# Backplane_Compact_R2_1.net
KiCad netlist of a schematic drawn in EAGLE
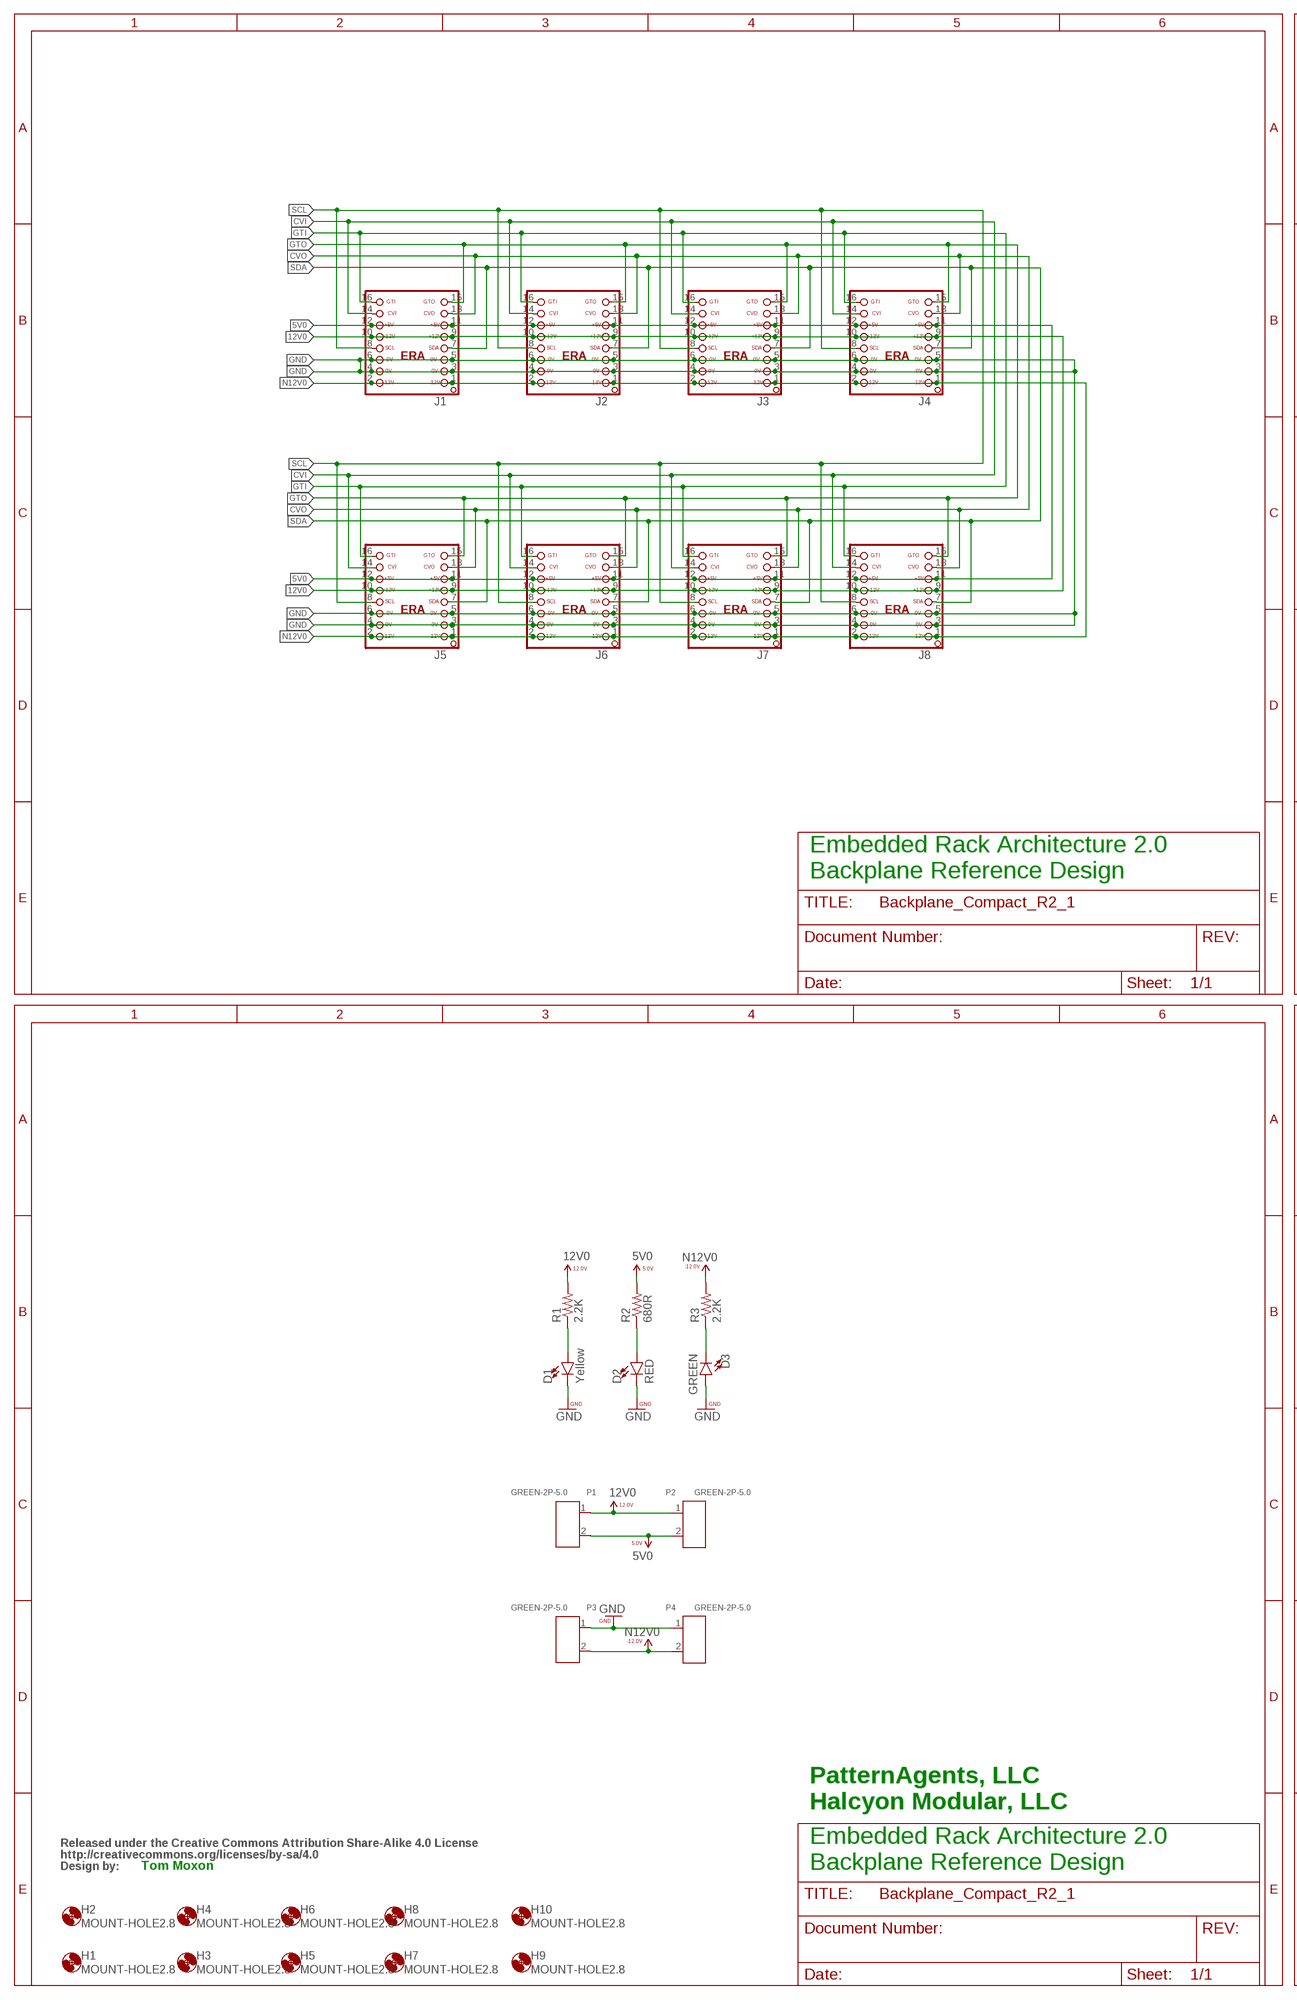
[diagram p0: schematic, sheet 1, part 1 of 2]
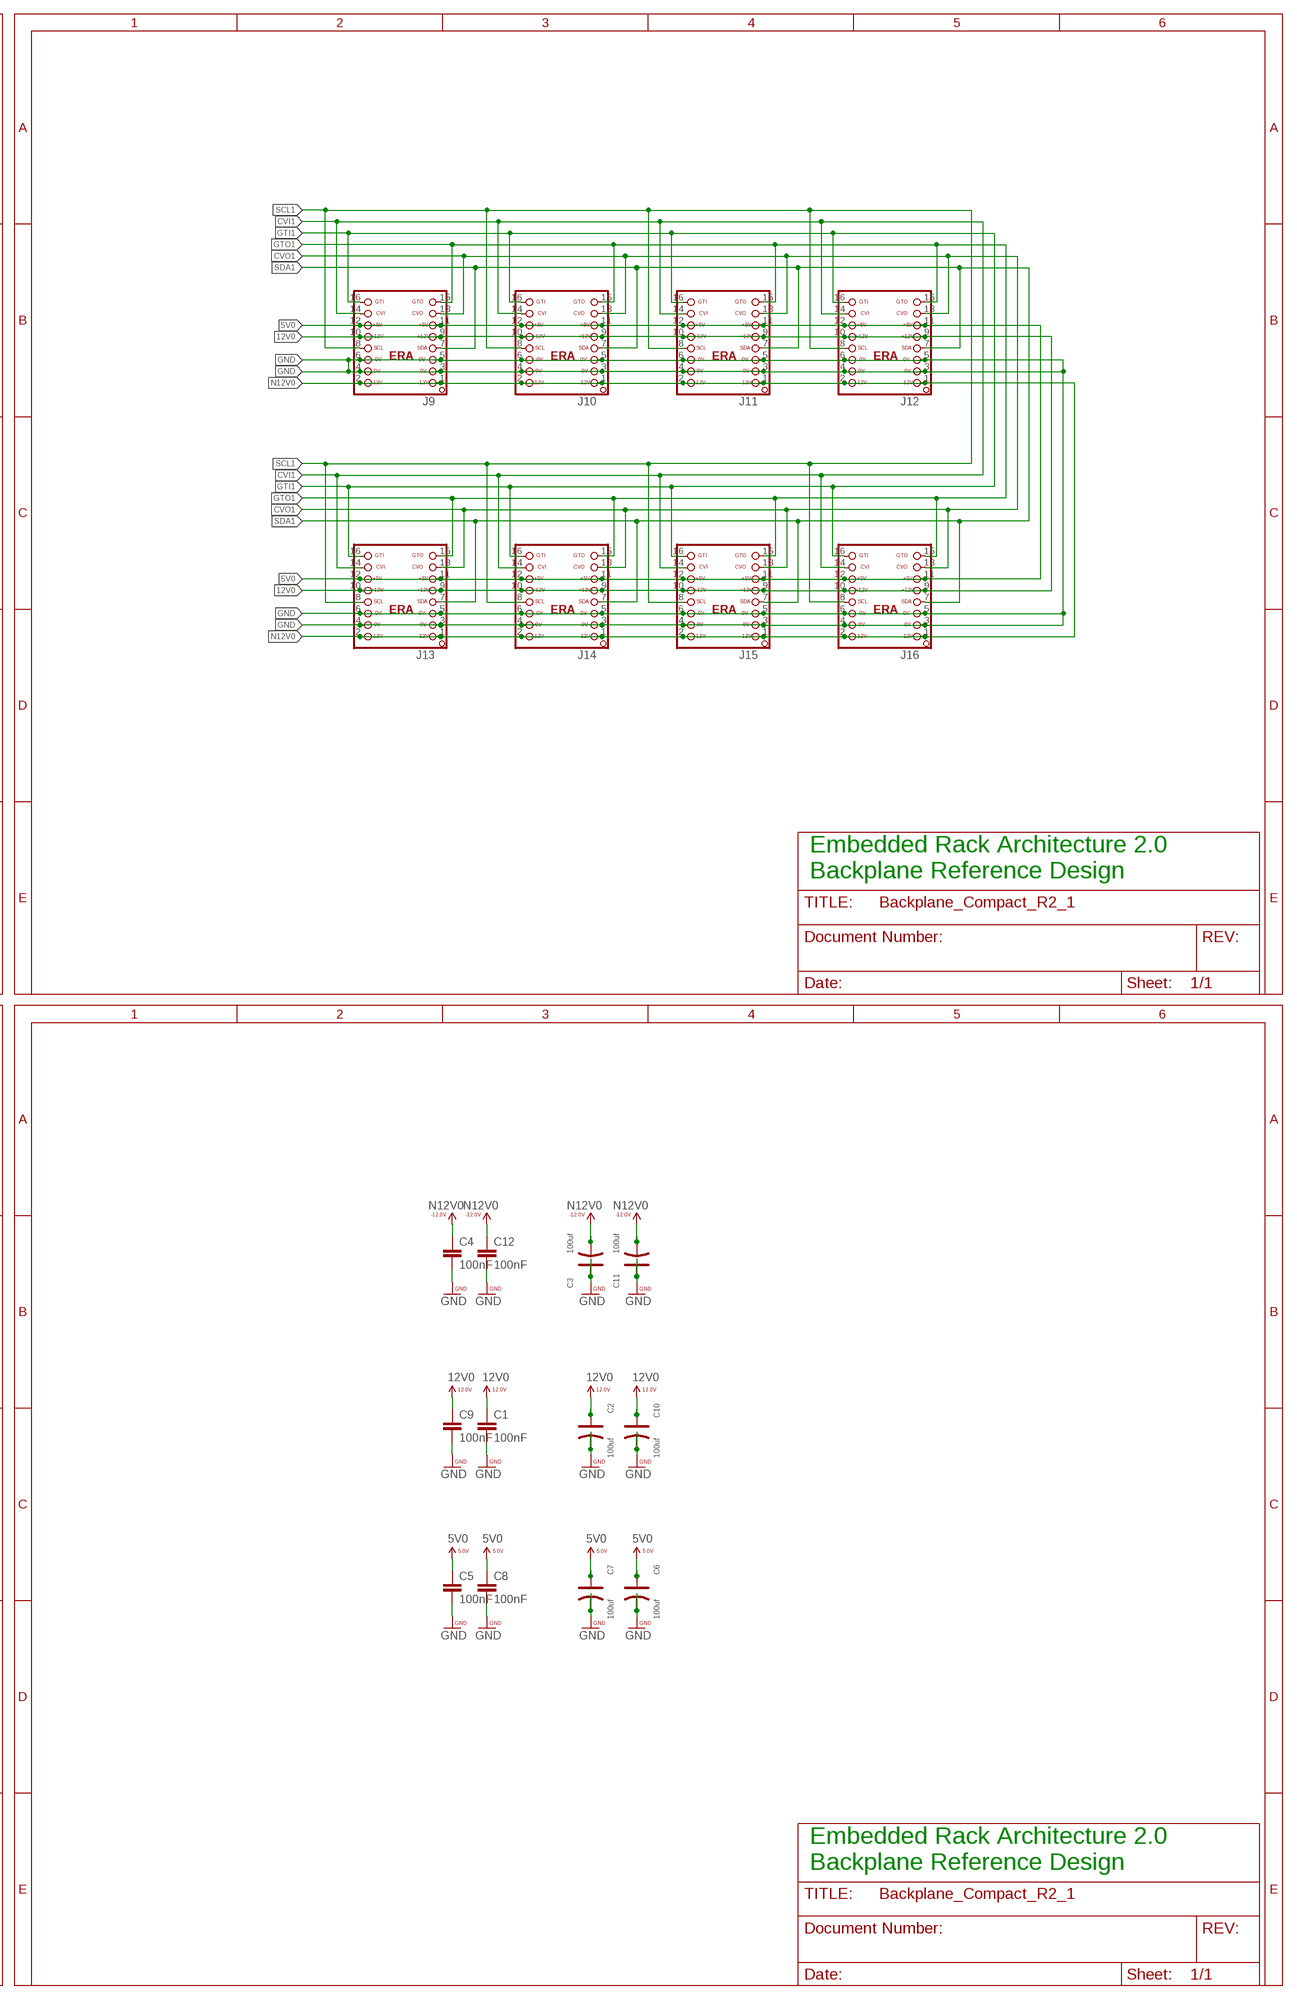
[diagram p1: schematic, sheet 1, part 2 of 2]

(export (version "E")
  (design (tool "Eeschema 10.0.6"))
  (components
    (comp (ref "C1")
      (value "100nF")
      (footprint "eagle-import:0603-CAP")
      (libsource (lib "eagle-import") (part "CAP0603-CAP"))
    )
    (comp (ref "C2")
      (value "100uf")
      (footprint "eagle-import:PC-D5.3MM")
      (fields (field (name "MPN") "KS 100uF/16V"))
      (libsource (lib "eagle-import") (part "DIP-ALUMINUM-100UF-16V(D5-H7MM)"))
    )
    (comp (ref "C3")
      (value "100uf")
      (footprint "eagle-import:PC-D5.3MM")
      (fields (field (name "MPN") "KS 100uF/16V"))
      (libsource (lib "eagle-import") (part "DIP-ALUMINUM-100UF-16V(D5-H7MM)"))
    )
    (comp (ref "C4")
      (value "100nF")
      (footprint "eagle-import:0603-CAP")
      (libsource (lib "eagle-import") (part "CAP0603-CAP"))
    )
    (comp (ref "C5")
      (value "100nF")
      (footprint "eagle-import:0603-CAP")
      (libsource (lib "eagle-import") (part "CAP0603-CAP"))
    )
    (comp (ref "C6")
      (value "100uf")
      (footprint "eagle-import:PC-D5.3MM")
      (fields (field (name "MPN") "KS 100uF/16V"))
      (libsource (lib "eagle-import") (part "DIP-ALUMINUM-100UF-16V(D5-H7MM)"))
    )
    (comp (ref "C7")
      (value "100uf")
      (footprint "eagle-import:PC-D5.3MM")
      (fields (field (name "MPN") "KS 100uF/16V"))
      (libsource (lib "eagle-import") (part "DIP-ALUMINUM-100UF-16V(D5-H7MM)"))
    )
    (comp (ref "C8")
      (value "100nF")
      (footprint "eagle-import:0603-CAP")
      (libsource (lib "eagle-import") (part "CAP0603-CAP"))
    )
    (comp (ref "C9")
      (value "100nF")
      (footprint "eagle-import:0603-CAP")
      (libsource (lib "eagle-import") (part "CAP0603-CAP"))
    )
    (comp (ref "C10")
      (value "100uf")
      (footprint "eagle-import:PC-D5.3MM")
      (fields (field (name "MPN") "KS 100uF/16V"))
      (libsource (lib "eagle-import") (part "DIP-ALUMINUM-100UF-16V(D5-H7MM)"))
    )
    (comp (ref "C11")
      (value "100uf")
      (footprint "eagle-import:PC-D5.3MM")
      (fields (field (name "MPN") "KS 100uF/16V"))
      (libsource (lib "eagle-import") (part "DIP-ALUMINUM-100UF-16V(D5-H7MM)"))
    )
    (comp (ref "C12")
      (value "100nF")
      (footprint "eagle-import:0603-CAP")
      (libsource (lib "eagle-import") (part "CAP0603-CAP"))
    )
    (comp (ref "D1")
      (value "Yellow")
      (footprint "eagle-import:LED-0603")
      (libsource (lib "eagle-import") (part "LED-YELLOW0603"))
    )
    (comp (ref "D2")
      (value "RED")
      (footprint "eagle-import:LED-0603")
      (libsource (lib "eagle-import") (part "LED-RED0603"))
    )
    (comp (ref "D3")
      (value "GREEN")
      (footprint "eagle-import:LED-0603")
      (libsource (lib "eagle-import") (part "LED-GREEN0603"))
    )
    (comp (ref "H1")
      (value "MOUNT-HOLE2.8")
      (footprint "eagle-import:2,8")
      (libsource (lib "eagle-import") (part "MOUNT-HOLE2.8"))
    )
    (comp (ref "H2")
      (value "MOUNT-HOLE2.8")
      (footprint "eagle-import:2,8")
      (libsource (lib "eagle-import") (part "MOUNT-HOLE2.8"))
    )
    (comp (ref "H3")
      (value "MOUNT-HOLE2.8")
      (footprint "eagle-import:2,8")
      (libsource (lib "eagle-import") (part "MOUNT-HOLE2.8"))
    )
    (comp (ref "H4")
      (value "MOUNT-HOLE2.8")
      (footprint "eagle-import:2,8")
      (libsource (lib "eagle-import") (part "MOUNT-HOLE2.8"))
    )
    (comp (ref "H5")
      (value "MOUNT-HOLE2.8")
      (footprint "eagle-import:2,8")
      (libsource (lib "eagle-import") (part "MOUNT-HOLE2.8"))
    )
    (comp (ref "H6")
      (value "MOUNT-HOLE2.8")
      (footprint "eagle-import:2,8")
      (libsource (lib "eagle-import") (part "MOUNT-HOLE2.8"))
    )
    (comp (ref "H7")
      (value "MOUNT-HOLE2.8")
      (footprint "eagle-import:2,8")
      (libsource (lib "eagle-import") (part "MOUNT-HOLE2.8"))
    )
    (comp (ref "H8")
      (value "MOUNT-HOLE2.8")
      (footprint "eagle-import:2,8")
      (libsource (lib "eagle-import") (part "MOUNT-HOLE2.8"))
    )
    (comp (ref "H9")
      (value "MOUNT-HOLE2.8")
      (footprint "eagle-import:2,8")
      (libsource (lib "eagle-import") (part "MOUNT-HOLE2.8"))
    )
    (comp (ref "H10")
      (value "MOUNT-HOLE2.8")
      (footprint "eagle-import:2,8")
      (libsource (lib "eagle-import") (part "MOUNT-HOLE2.8"))
    )
    (comp (ref "J1")
      (value "ERA-SHROUD")
      (footprint "eagle-import:ERA")
      (libsource (lib "eagle-import") (part "ERA-SHROUD"))
    )
    (comp (ref "J2")
      (value "ERA-SHROUD")
      (footprint "eagle-import:ERA")
      (libsource (lib "eagle-import") (part "ERA-SHROUD"))
    )
    (comp (ref "J3")
      (value "ERA-SHROUD")
      (footprint "eagle-import:ERA")
      (libsource (lib "eagle-import") (part "ERA-SHROUD"))
    )
    (comp (ref "J4")
      (value "ERA-SHROUD")
      (footprint "eagle-import:ERA")
      (libsource (lib "eagle-import") (part "ERA-SHROUD"))
    )
    (comp (ref "J5")
      (value "ERA-SHROUD")
      (footprint "eagle-import:ERA")
      (libsource (lib "eagle-import") (part "ERA-SHROUD"))
    )
    (comp (ref "J6")
      (value "ERA-SHROUD")
      (footprint "eagle-import:ERA")
      (libsource (lib "eagle-import") (part "ERA-SHROUD"))
    )
    (comp (ref "J7")
      (value "ERA-SHROUD")
      (footprint "eagle-import:ERA")
      (libsource (lib "eagle-import") (part "ERA-SHROUD"))
    )
    (comp (ref "J8")
      (value "ERA-SHROUD")
      (footprint "eagle-import:ERA")
      (libsource (lib "eagle-import") (part "ERA-SHROUD"))
    )
    (comp (ref "J9")
      (value "ERA-SHROUD")
      (footprint "eagle-import:ERA")
      (libsource (lib "eagle-import") (part "ERA-SHROUD"))
    )
    (comp (ref "J10")
      (value "ERA-SHROUD")
      (footprint "eagle-import:ERA")
      (libsource (lib "eagle-import") (part "ERA-SHROUD"))
    )
    (comp (ref "J11")
      (value "ERA-SHROUD")
      (footprint "eagle-import:ERA")
      (libsource (lib "eagle-import") (part "ERA-SHROUD"))
    )
    (comp (ref "J12")
      (value "ERA-SHROUD")
      (footprint "eagle-import:ERA")
      (libsource (lib "eagle-import") (part "ERA-SHROUD"))
    )
    (comp (ref "J13")
      (value "ERA-SHROUD")
      (footprint "eagle-import:ERA")
      (libsource (lib "eagle-import") (part "ERA-SHROUD"))
    )
    (comp (ref "J14")
      (value "ERA-SHROUD")
      (footprint "eagle-import:ERA")
      (libsource (lib "eagle-import") (part "ERA-SHROUD"))
    )
    (comp (ref "J15")
      (value "ERA-SHROUD")
      (footprint "eagle-import:ERA")
      (libsource (lib "eagle-import") (part "ERA-SHROUD"))
    )
    (comp (ref "J16")
      (value "ERA-SHROUD")
      (footprint "eagle-import:ERA")
      (libsource (lib "eagle-import") (part "ERA-SHROUD"))
    )
    (comp (ref "P1")
      (value "GREEN-2P-5.0")
      (footprint "eagle-import:H2-5.0-10.5X8.0MM")
      (libsource (lib "eagle-import") (part "SCREW-TERMINAL-GREEN(2P-5.0)"))
    )
    (comp (ref "P2")
      (value "GREEN-2P-5.0")
      (footprint "eagle-import:H2-5.0-10.5X8.0MM")
      (libsource (lib "eagle-import") (part "SCREW-TERMINAL-GREEN(2P-5.0)"))
    )
    (comp (ref "P3")
      (value "GREEN-2P-5.0")
      (footprint "eagle-import:H2-5.0-10.5X8.0MM")
      (libsource (lib "eagle-import") (part "SCREW-TERMINAL-GREEN(2P-5.0)"))
    )
    (comp (ref "P4")
      (value "GREEN-2P-5.0")
      (footprint "eagle-import:H2-5.0-10.5X8.0MM")
      (libsource (lib "eagle-import") (part "SCREW-TERMINAL-GREEN(2P-5.0)"))
    )
    (comp (ref "R1")
      (value "2.2K")
      (footprint "eagle-import:0603-RES")
      (libsource (lib "eagle-import") (part "RESISTOR0603"))
    )
    (comp (ref "R2")
      (value "680R")
      (footprint "eagle-import:0603-RES")
      (libsource (lib "eagle-import") (part "RESISTOR0603"))
    )
    (comp (ref "R3")
      (value "2.2K")
      (footprint "eagle-import:0603-RES")
      (libsource (lib "eagle-import") (part "RESISTOR0603"))
    )
    (comp (ref "U$48")
      (value "BY_CC_SA_TEXTTEXT")
      (footprint "eagle-import:BY_CC_SA_TEXT")
      (libsource (lib "eagle-import") (part "BY_CC_SA_TEXTTEXT"))
    )
  )
  (nets
    (net (code "1") (name "5V0") (class "Default")
      (node (ref "C5") (pin "1") (pinfunction "1_1") (pintype "passive"))
      (node (ref "C6") (pin "+") (pinfunction "+_+") (pintype "passive"))
      (node (ref "C7") (pin "+") (pinfunction "+_+") (pintype "passive"))
      (node (ref "C8") (pin "1") (pinfunction "1_1") (pintype "passive"))
      (node (ref "J1") (pin "11") (pinfunction "11_11") (pintype "passive"))
      (node (ref "J1") (pin "12") (pinfunction "12_12") (pintype "passive"))
      (node (ref "J10") (pin "11") (pinfunction "11_11") (pintype "passive"))
      (node (ref "J10") (pin "12") (pinfunction "12_12") (pintype "passive"))
      (node (ref "J11") (pin "11") (pinfunction "11_11") (pintype "passive"))
      (node (ref "J11") (pin "12") (pinfunction "12_12") (pintype "passive"))
      (node (ref "J12") (pin "11") (pinfunction "11_11") (pintype "passive"))
      (node (ref "J12") (pin "12") (pinfunction "12_12") (pintype "passive"))
      (node (ref "J13") (pin "11") (pinfunction "11_11") (pintype "passive"))
      (node (ref "J13") (pin "12") (pinfunction "12_12") (pintype "passive"))
      (node (ref "J14") (pin "11") (pinfunction "11_11") (pintype "passive"))
      (node (ref "J14") (pin "12") (pinfunction "12_12") (pintype "passive"))
      (node (ref "J15") (pin "11") (pinfunction "11_11") (pintype "passive"))
      (node (ref "J15") (pin "12") (pinfunction "12_12") (pintype "passive"))
      (node (ref "J16") (pin "11") (pinfunction "11_11") (pintype "passive"))
      (node (ref "J16") (pin "12") (pinfunction "12_12") (pintype "passive"))
      (node (ref "J2") (pin "11") (pinfunction "11_11") (pintype "passive"))
      (node (ref "J2") (pin "12") (pinfunction "12_12") (pintype "passive"))
      (node (ref "J3") (pin "11") (pinfunction "11_11") (pintype "passive"))
      (node (ref "J3") (pin "12") (pinfunction "12_12") (pintype "passive"))
      (node (ref "J4") (pin "11") (pinfunction "11_11") (pintype "passive"))
      (node (ref "J4") (pin "12") (pinfunction "12_12") (pintype "passive"))
      (node (ref "J5") (pin "11") (pinfunction "11_11") (pintype "passive"))
      (node (ref "J5") (pin "12") (pinfunction "12_12") (pintype "passive"))
      (node (ref "J6") (pin "11") (pinfunction "11_11") (pintype "passive"))
      (node (ref "J6") (pin "12") (pinfunction "12_12") (pintype "passive"))
      (node (ref "J7") (pin "11") (pinfunction "11_11") (pintype "passive"))
      (node (ref "J7") (pin "12") (pinfunction "12_12") (pintype "passive"))
      (node (ref "J8") (pin "11") (pinfunction "11_11") (pintype "passive"))
      (node (ref "J8") (pin "12") (pinfunction "12_12") (pintype "passive"))
      (node (ref "J9") (pin "11") (pinfunction "11_11") (pintype "passive"))
      (node (ref "J9") (pin "12") (pinfunction "12_12") (pintype "passive"))
      (node (ref "P1") (pin "2") (pinfunction "2_2") (pintype "bidirectional"))
      (node (ref "P2") (pin "2") (pinfunction "2_2") (pintype "bidirectional"))
      (node (ref "R2") (pin "2") (pinfunction "2_2") (pintype "passive"))
    )
    (net (code "2") (name "12V0") (class "Default")
      (node (ref "C1") (pin "1") (pinfunction "1_1") (pintype "passive"))
      (node (ref "C10") (pin "+") (pinfunction "+_+") (pintype "passive"))
      (node (ref "C2") (pin "+") (pinfunction "+_+") (pintype "passive"))
      (node (ref "C9") (pin "1") (pinfunction "1_1") (pintype "passive"))
      (node (ref "J1") (pin "10") (pinfunction "10_10") (pintype "passive"))
      (node (ref "J1") (pin "9") (pinfunction "9_9") (pintype "passive"))
      (node (ref "J10") (pin "10") (pinfunction "10_10") (pintype "passive"))
      (node (ref "J10") (pin "9") (pinfunction "9_9") (pintype "passive"))
      (node (ref "J11") (pin "10") (pinfunction "10_10") (pintype "passive"))
      (node (ref "J11") (pin "9") (pinfunction "9_9") (pintype "passive"))
      (node (ref "J12") (pin "10") (pinfunction "10_10") (pintype "passive"))
      (node (ref "J12") (pin "9") (pinfunction "9_9") (pintype "passive"))
      (node (ref "J13") (pin "10") (pinfunction "10_10") (pintype "passive"))
      (node (ref "J13") (pin "9") (pinfunction "9_9") (pintype "passive"))
      (node (ref "J14") (pin "10") (pinfunction "10_10") (pintype "passive"))
      (node (ref "J14") (pin "9") (pinfunction "9_9") (pintype "passive"))
      (node (ref "J15") (pin "10") (pinfunction "10_10") (pintype "passive"))
      (node (ref "J15") (pin "9") (pinfunction "9_9") (pintype "passive"))
      (node (ref "J16") (pin "10") (pinfunction "10_10") (pintype "passive"))
      (node (ref "J16") (pin "9") (pinfunction "9_9") (pintype "passive"))
      (node (ref "J2") (pin "10") (pinfunction "10_10") (pintype "passive"))
      (node (ref "J2") (pin "9") (pinfunction "9_9") (pintype "passive"))
      (node (ref "J3") (pin "10") (pinfunction "10_10") (pintype "passive"))
      (node (ref "J3") (pin "9") (pinfunction "9_9") (pintype "passive"))
      (node (ref "J4") (pin "10") (pinfunction "10_10") (pintype "passive"))
      (node (ref "J4") (pin "9") (pinfunction "9_9") (pintype "passive"))
      (node (ref "J5") (pin "10") (pinfunction "10_10") (pintype "passive"))
      (node (ref "J5") (pin "9") (pinfunction "9_9") (pintype "passive"))
      (node (ref "J6") (pin "10") (pinfunction "10_10") (pintype "passive"))
      (node (ref "J6") (pin "9") (pinfunction "9_9") (pintype "passive"))
      (node (ref "J7") (pin "10") (pinfunction "10_10") (pintype "passive"))
      (node (ref "J7") (pin "9") (pinfunction "9_9") (pintype "passive"))
      (node (ref "J8") (pin "10") (pinfunction "10_10") (pintype "passive"))
      (node (ref "J8") (pin "9") (pinfunction "9_9") (pintype "passive"))
      (node (ref "J9") (pin "10") (pinfunction "10_10") (pintype "passive"))
      (node (ref "J9") (pin "9") (pinfunction "9_9") (pintype "passive"))
      (node (ref "P1") (pin "1") (pinfunction "1_1") (pintype "bidirectional"))
      (node (ref "P2") (pin "1") (pinfunction "1_1") (pintype "bidirectional"))
      (node (ref "R1") (pin "2") (pinfunction "2_2") (pintype "passive"))
    )
    (net (code "3") (name "CVI") (class "Default")
      (node (ref "J1") (pin "14") (pinfunction "14_14") (pintype "passive"))
      (node (ref "J2") (pin "14") (pinfunction "14_14") (pintype "passive"))
      (node (ref "J3") (pin "14") (pinfunction "14_14") (pintype "passive"))
      (node (ref "J4") (pin "14") (pinfunction "14_14") (pintype "passive"))
      (node (ref "J5") (pin "14") (pinfunction "14_14") (pintype "passive"))
      (node (ref "J6") (pin "14") (pinfunction "14_14") (pintype "passive"))
      (node (ref "J7") (pin "14") (pinfunction "14_14") (pintype "passive"))
      (node (ref "J8") (pin "14") (pinfunction "14_14") (pintype "passive"))
    )
    (net (code "4") (name "CVI1") (class "Default")
      (node (ref "J10") (pin "14") (pinfunction "14_14") (pintype "passive"))
      (node (ref "J11") (pin "14") (pinfunction "14_14") (pintype "passive"))
      (node (ref "J12") (pin "14") (pinfunction "14_14") (pintype "passive"))
      (node (ref "J13") (pin "14") (pinfunction "14_14") (pintype "passive"))
      (node (ref "J14") (pin "14") (pinfunction "14_14") (pintype "passive"))
      (node (ref "J15") (pin "14") (pinfunction "14_14") (pintype "passive"))
      (node (ref "J16") (pin "14") (pinfunction "14_14") (pintype "passive"))
      (node (ref "J9") (pin "14") (pinfunction "14_14") (pintype "passive"))
    )
    (net (code "5") (name "CVO") (class "Default")
      (node (ref "J1") (pin "13") (pinfunction "13_13") (pintype "passive"))
      (node (ref "J2") (pin "13") (pinfunction "13_13") (pintype "passive"))
      (node (ref "J3") (pin "13") (pinfunction "13_13") (pintype "passive"))
      (node (ref "J4") (pin "13") (pinfunction "13_13") (pintype "passive"))
      (node (ref "J5") (pin "13") (pinfunction "13_13") (pintype "passive"))
      (node (ref "J6") (pin "13") (pinfunction "13_13") (pintype "passive"))
      (node (ref "J7") (pin "13") (pinfunction "13_13") (pintype "passive"))
      (node (ref "J8") (pin "13") (pinfunction "13_13") (pintype "passive"))
    )
    (net (code "6") (name "CVO1") (class "Default")
      (node (ref "J10") (pin "13") (pinfunction "13_13") (pintype "passive"))
      (node (ref "J11") (pin "13") (pinfunction "13_13") (pintype "passive"))
      (node (ref "J12") (pin "13") (pinfunction "13_13") (pintype "passive"))
      (node (ref "J13") (pin "13") (pinfunction "13_13") (pintype "passive"))
      (node (ref "J14") (pin "13") (pinfunction "13_13") (pintype "passive"))
      (node (ref "J15") (pin "13") (pinfunction "13_13") (pintype "passive"))
      (node (ref "J16") (pin "13") (pinfunction "13_13") (pintype "passive"))
      (node (ref "J9") (pin "13") (pinfunction "13_13") (pintype "passive"))
    )
    (net (code "7") (name "GND") (class "Default")
      (node (ref "C1") (pin "2") (pinfunction "2_2") (pintype "passive"))
      (node (ref "C10") (pin "-") (pinfunction "-_-") (pintype "passive"))
      (node (ref "C11") (pin "+") (pinfunction "+_+") (pintype "passive"))
      (node (ref "C12") (pin "2") (pinfunction "2_2") (pintype "passive"))
      (node (ref "C2") (pin "-") (pinfunction "-_-") (pintype "passive"))
      (node (ref "C3") (pin "+") (pinfunction "+_+") (pintype "passive"))
      (node (ref "C4") (pin "2") (pinfunction "2_2") (pintype "passive"))
      (node (ref "C5") (pin "2") (pinfunction "2_2") (pintype "passive"))
      (node (ref "C6") (pin "-") (pinfunction "-_-") (pintype "passive"))
      (node (ref "C7") (pin "-") (pinfunction "-_-") (pintype "passive"))
      (node (ref "C8") (pin "2") (pinfunction "2_2") (pintype "passive"))
      (node (ref "C9") (pin "2") (pinfunction "2_2") (pintype "passive"))
      (node (ref "D1") (pin "C") (pinfunction "C_C") (pintype "passive"))
      (node (ref "D2") (pin "C") (pinfunction "C_C") (pintype "passive"))
      (node (ref "D3") (pin "A") (pinfunction "A_A") (pintype "passive"))
      (node (ref "J1") (pin "3") (pinfunction "3_3") (pintype "passive"))
      (node (ref "J1") (pin "4") (pinfunction "4_4") (pintype "passive"))
      (node (ref "J1") (pin "5") (pinfunction "5_5") (pintype "passive"))
      (node (ref "J1") (pin "6") (pinfunction "6_6") (pintype "passive"))
      (node (ref "J10") (pin "3") (pinfunction "3_3") (pintype "passive"))
      (node (ref "J10") (pin "4") (pinfunction "4_4") (pintype "passive"))
      (node (ref "J10") (pin "5") (pinfunction "5_5") (pintype "passive"))
      (node (ref "J10") (pin "6") (pinfunction "6_6") (pintype "passive"))
      (node (ref "J11") (pin "3") (pinfunction "3_3") (pintype "passive"))
      (node (ref "J11") (pin "4") (pinfunction "4_4") (pintype "passive"))
      (node (ref "J11") (pin "5") (pinfunction "5_5") (pintype "passive"))
      (node (ref "J11") (pin "6") (pinfunction "6_6") (pintype "passive"))
      (node (ref "J12") (pin "3") (pinfunction "3_3") (pintype "passive"))
      (node (ref "J12") (pin "4") (pinfunction "4_4") (pintype "passive"))
      (node (ref "J12") (pin "5") (pinfunction "5_5") (pintype "passive"))
      (node (ref "J12") (pin "6") (pinfunction "6_6") (pintype "passive"))
      (node (ref "J13") (pin "3") (pinfunction "3_3") (pintype "passive"))
      (node (ref "J13") (pin "4") (pinfunction "4_4") (pintype "passive"))
      (node (ref "J13") (pin "5") (pinfunction "5_5") (pintype "passive"))
      (node (ref "J13") (pin "6") (pinfunction "6_6") (pintype "passive"))
      (node (ref "J14") (pin "3") (pinfunction "3_3") (pintype "passive"))
      (node (ref "J14") (pin "4") (pinfunction "4_4") (pintype "passive"))
      (node (ref "J14") (pin "5") (pinfunction "5_5") (pintype "passive"))
      (node (ref "J14") (pin "6") (pinfunction "6_6") (pintype "passive"))
      (node (ref "J15") (pin "3") (pinfunction "3_3") (pintype "passive"))
      (node (ref "J15") (pin "4") (pinfunction "4_4") (pintype "passive"))
      (node (ref "J15") (pin "5") (pinfunction "5_5") (pintype "passive"))
      (node (ref "J15") (pin "6") (pinfunction "6_6") (pintype "passive"))
      (node (ref "J16") (pin "3") (pinfunction "3_3") (pintype "passive"))
      (node (ref "J16") (pin "4") (pinfunction "4_4") (pintype "passive"))
      (node (ref "J16") (pin "5") (pinfunction "5_5") (pintype "passive"))
      (node (ref "J16") (pin "6") (pinfunction "6_6") (pintype "passive"))
      (node (ref "J2") (pin "3") (pinfunction "3_3") (pintype "passive"))
      (node (ref "J2") (pin "4") (pinfunction "4_4") (pintype "passive"))
      (node (ref "J2") (pin "5") (pinfunction "5_5") (pintype "passive"))
      (node (ref "J2") (pin "6") (pinfunction "6_6") (pintype "passive"))
      (node (ref "J3") (pin "3") (pinfunction "3_3") (pintype "passive"))
      (node (ref "J3") (pin "4") (pinfunction "4_4") (pintype "passive"))
      (node (ref "J3") (pin "5") (pinfunction "5_5") (pintype "passive"))
      (node (ref "J3") (pin "6") (pinfunction "6_6") (pintype "passive"))
      (node (ref "J4") (pin "3") (pinfunction "3_3") (pintype "passive"))
      (node (ref "J4") (pin "4") (pinfunction "4_4") (pintype "passive"))
      (node (ref "J4") (pin "5") (pinfunction "5_5") (pintype "passive"))
      (node (ref "J4") (pin "6") (pinfunction "6_6") (pintype "passive"))
      (node (ref "J5") (pin "3") (pinfunction "3_3") (pintype "passive"))
      (node (ref "J5") (pin "4") (pinfunction "4_4") (pintype "passive"))
      (node (ref "J5") (pin "5") (pinfunction "5_5") (pintype "passive"))
      (node (ref "J5") (pin "6") (pinfunction "6_6") (pintype "passive"))
      (node (ref "J6") (pin "3") (pinfunction "3_3") (pintype "passive"))
      (node (ref "J6") (pin "4") (pinfunction "4_4") (pintype "passive"))
      (node (ref "J6") (pin "5") (pinfunction "5_5") (pintype "passive"))
      (node (ref "J6") (pin "6") (pinfunction "6_6") (pintype "passive"))
      (node (ref "J7") (pin "3") (pinfunction "3_3") (pintype "passive"))
      (node (ref "J7") (pin "4") (pinfunction "4_4") (pintype "passive"))
      (node (ref "J7") (pin "5") (pinfunction "5_5") (pintype "passive"))
      (node (ref "J7") (pin "6") (pinfunction "6_6") (pintype "passive"))
      (node (ref "J8") (pin "3") (pinfunction "3_3") (pintype "passive"))
      (node (ref "J8") (pin "4") (pinfunction "4_4") (pintype "passive"))
      (node (ref "J8") (pin "5") (pinfunction "5_5") (pintype "passive"))
      (node (ref "J8") (pin "6") (pinfunction "6_6") (pintype "passive"))
      (node (ref "J9") (pin "3") (pinfunction "3_3") (pintype "passive"))
      (node (ref "J9") (pin "4") (pinfunction "4_4") (pintype "passive"))
      (node (ref "J9") (pin "5") (pinfunction "5_5") (pintype "passive"))
      (node (ref "J9") (pin "6") (pinfunction "6_6") (pintype "passive"))
      (node (ref "P3") (pin "1") (pinfunction "1_1") (pintype "bidirectional"))
      (node (ref "P4") (pin "1") (pinfunction "1_1") (pintype "bidirectional"))
    )
    (net (code "8") (name "GTI") (class "Default")
      (node (ref "J1") (pin "16") (pinfunction "16_16") (pintype "passive"))
      (node (ref "J2") (pin "16") (pinfunction "16_16") (pintype "passive"))
      (node (ref "J3") (pin "16") (pinfunction "16_16") (pintype "passive"))
      (node (ref "J4") (pin "16") (pinfunction "16_16") (pintype "passive"))
      (node (ref "J5") (pin "16") (pinfunction "16_16") (pintype "passive"))
      (node (ref "J6") (pin "16") (pinfunction "16_16") (pintype "passive"))
      (node (ref "J7") (pin "16") (pinfunction "16_16") (pintype "passive"))
      (node (ref "J8") (pin "16") (pinfunction "16_16") (pintype "passive"))
    )
    (net (code "9") (name "GTI1") (class "Default")
      (node (ref "J10") (pin "16") (pinfunction "16_16") (pintype "passive"))
      (node (ref "J11") (pin "16") (pinfunction "16_16") (pintype "passive"))
      (node (ref "J12") (pin "16") (pinfunction "16_16") (pintype "passive"))
      (node (ref "J13") (pin "16") (pinfunction "16_16") (pintype "passive"))
      (node (ref "J14") (pin "16") (pinfunction "16_16") (pintype "passive"))
      (node (ref "J15") (pin "16") (pinfunction "16_16") (pintype "passive"))
      (node (ref "J16") (pin "16") (pinfunction "16_16") (pintype "passive"))
      (node (ref "J9") (pin "16") (pinfunction "16_16") (pintype "passive"))
    )
    (net (code "10") (name "GTO") (class "Default")
      (node (ref "J1") (pin "15") (pinfunction "15_15") (pintype "passive"))
      (node (ref "J2") (pin "15") (pinfunction "15_15") (pintype "passive"))
      (node (ref "J3") (pin "15") (pinfunction "15_15") (pintype "passive"))
      (node (ref "J4") (pin "15") (pinfunction "15_15") (pintype "passive"))
      (node (ref "J5") (pin "15") (pinfunction "15_15") (pintype "passive"))
      (node (ref "J6") (pin "15") (pinfunction "15_15") (pintype "passive"))
      (node (ref "J7") (pin "15") (pinfunction "15_15") (pintype "passive"))
      (node (ref "J8") (pin "15") (pinfunction "15_15") (pintype "passive"))
    )
    (net (code "11") (name "GTO1") (class "Default")
      (node (ref "J10") (pin "15") (pinfunction "15_15") (pintype "passive"))
      (node (ref "J11") (pin "15") (pinfunction "15_15") (pintype "passive"))
      (node (ref "J12") (pin "15") (pinfunction "15_15") (pintype "passive"))
      (node (ref "J13") (pin "15") (pinfunction "15_15") (pintype "passive"))
      (node (ref "J14") (pin "15") (pinfunction "15_15") (pintype "passive"))
      (node (ref "J15") (pin "15") (pinfunction "15_15") (pintype "passive"))
      (node (ref "J16") (pin "15") (pinfunction "15_15") (pintype "passive"))
      (node (ref "J9") (pin "15") (pinfunction "15_15") (pintype "passive"))
    )
    (net (code "12") (name "N12V0") (class "Default")
      (node (ref "C11") (pin "-") (pinfunction "-_-") (pintype "passive"))
      (node (ref "C12") (pin "1") (pinfunction "1_1") (pintype "passive"))
      (node (ref "C3") (pin "-") (pinfunction "-_-") (pintype "passive"))
      (node (ref "C4") (pin "1") (pinfunction "1_1") (pintype "passive"))
      (node (ref "J1") (pin "1") (pinfunction "1_1") (pintype "passive"))
      (node (ref "J1") (pin "2") (pinfunction "2_2") (pintype "passive"))
      (node (ref "J10") (pin "1") (pinfunction "1_1") (pintype "passive"))
      (node (ref "J10") (pin "2") (pinfunction "2_2") (pintype "passive"))
      (node (ref "J11") (pin "1") (pinfunction "1_1") (pintype "passive"))
      (node (ref "J11") (pin "2") (pinfunction "2_2") (pintype "passive"))
      (node (ref "J12") (pin "1") (pinfunction "1_1") (pintype "passive"))
      (node (ref "J12") (pin "2") (pinfunction "2_2") (pintype "passive"))
      (node (ref "J13") (pin "1") (pinfunction "1_1") (pintype "passive"))
      (node (ref "J13") (pin "2") (pinfunction "2_2") (pintype "passive"))
      (node (ref "J14") (pin "1") (pinfunction "1_1") (pintype "passive"))
      (node (ref "J14") (pin "2") (pinfunction "2_2") (pintype "passive"))
      (node (ref "J15") (pin "1") (pinfunction "1_1") (pintype "passive"))
      (node (ref "J15") (pin "2") (pinfunction "2_2") (pintype "passive"))
      (node (ref "J16") (pin "1") (pinfunction "1_1") (pintype "passive"))
      (node (ref "J16") (pin "2") (pinfunction "2_2") (pintype "passive"))
      (node (ref "J2") (pin "1") (pinfunction "1_1") (pintype "passive"))
      (node (ref "J2") (pin "2") (pinfunction "2_2") (pintype "passive"))
      (node (ref "J3") (pin "1") (pinfunction "1_1") (pintype "passive"))
      (node (ref "J3") (pin "2") (pinfunction "2_2") (pintype "passive"))
      (node (ref "J4") (pin "1") (pinfunction "1_1") (pintype "passive"))
      (node (ref "J4") (pin "2") (pinfunction "2_2") (pintype "passive"))
      (node (ref "J5") (pin "1") (pinfunction "1_1") (pintype "passive"))
      (node (ref "J5") (pin "2") (pinfunction "2_2") (pintype "passive"))
      (node (ref "J6") (pin "1") (pinfunction "1_1") (pintype "passive"))
      (node (ref "J6") (pin "2") (pinfunction "2_2") (pintype "passive"))
      (node (ref "J7") (pin "1") (pinfunction "1_1") (pintype "passive"))
      (node (ref "J7") (pin "2") (pinfunction "2_2") (pintype "passive"))
      (node (ref "J8") (pin "1") (pinfunction "1_1") (pintype "passive"))
      (node (ref "J8") (pin "2") (pinfunction "2_2") (pintype "passive"))
      (node (ref "J9") (pin "1") (pinfunction "1_1") (pintype "passive"))
      (node (ref "J9") (pin "2") (pinfunction "2_2") (pintype "passive"))
      (node (ref "P3") (pin "2") (pinfunction "2_2") (pintype "bidirectional"))
      (node (ref "P4") (pin "2") (pinfunction "2_2") (pintype "bidirectional"))
      (node (ref "R3") (pin "2") (pinfunction "2_2") (pintype "passive"))
    )
    (net (code "13") (name "Net-(D1-PadA)") (class "Default")
      (node (ref "D1") (pin "A") (pinfunction "A_A") (pintype "passive"))
      (node (ref "R1") (pin "1") (pinfunction "1_1") (pintype "passive"))
    )
    (net (code "14") (name "Net-(D2-PadA)") (class "Default")
      (node (ref "D2") (pin "A") (pinfunction "A_A") (pintype "passive"))
      (node (ref "R2") (pin "1") (pinfunction "1_1") (pintype "passive"))
    )
    (net (code "15") (name "Net-(D3-PadC)") (class "Default")
      (node (ref "D3") (pin "C") (pinfunction "C_C") (pintype "passive"))
      (node (ref "R3") (pin "1") (pinfunction "1_1") (pintype "passive"))
    )
    (net (code "16") (name "SCL") (class "Default")
      (node (ref "J1") (pin "8") (pinfunction "8_8") (pintype "passive"))
      (node (ref "J2") (pin "8") (pinfunction "8_8") (pintype "passive"))
      (node (ref "J3") (pin "8") (pinfunction "8_8") (pintype "passive"))
      (node (ref "J4") (pin "8") (pinfunction "8_8") (pintype "passive"))
      (node (ref "J5") (pin "8") (pinfunction "8_8") (pintype "passive"))
      (node (ref "J6") (pin "8") (pinfunction "8_8") (pintype "passive"))
      (node (ref "J7") (pin "8") (pinfunction "8_8") (pintype "passive"))
      (node (ref "J8") (pin "8") (pinfunction "8_8") (pintype "passive"))
    )
    (net (code "17") (name "SCL1") (class "Default")
      (node (ref "J10") (pin "8") (pinfunction "8_8") (pintype "passive"))
      (node (ref "J11") (pin "8") (pinfunction "8_8") (pintype "passive"))
      (node (ref "J12") (pin "8") (pinfunction "8_8") (pintype "passive"))
      (node (ref "J13") (pin "8") (pinfunction "8_8") (pintype "passive"))
      (node (ref "J14") (pin "8") (pinfunction "8_8") (pintype "passive"))
      (node (ref "J15") (pin "8") (pinfunction "8_8") (pintype "passive"))
      (node (ref "J16") (pin "8") (pinfunction "8_8") (pintype "passive"))
      (node (ref "J9") (pin "8") (pinfunction "8_8") (pintype "passive"))
    )
    (net (code "18") (name "SDA") (class "Default")
      (node (ref "J1") (pin "7") (pinfunction "7_7") (pintype "passive"))
      (node (ref "J2") (pin "7") (pinfunction "7_7") (pintype "passive"))
      (node (ref "J3") (pin "7") (pinfunction "7_7") (pintype "passive"))
      (node (ref "J4") (pin "7") (pinfunction "7_7") (pintype "passive"))
      (node (ref "J5") (pin "7") (pinfunction "7_7") (pintype "passive"))
      (node (ref "J6") (pin "7") (pinfunction "7_7") (pintype "passive"))
      (node (ref "J7") (pin "7") (pinfunction "7_7") (pintype "passive"))
      (node (ref "J8") (pin "7") (pinfunction "7_7") (pintype "passive"))
    )
    (net (code "19") (name "SDA1") (class "Default")
      (node (ref "J10") (pin "7") (pinfunction "7_7") (pintype "passive"))
      (node (ref "J11") (pin "7") (pinfunction "7_7") (pintype "passive"))
      (node (ref "J12") (pin "7") (pinfunction "7_7") (pintype "passive"))
      (node (ref "J13") (pin "7") (pinfunction "7_7") (pintype "passive"))
      (node (ref "J14") (pin "7") (pinfunction "7_7") (pintype "passive"))
      (node (ref "J15") (pin "7") (pinfunction "7_7") (pintype "passive"))
      (node (ref "J16") (pin "7") (pinfunction "7_7") (pintype "passive"))
      (node (ref "J9") (pin "7") (pinfunction "7_7") (pintype "passive"))
    )
  )
)
